# PROB_S7CAS_FPGA_3.net
KiCad netlist of a schematic drawn in Altium Designer
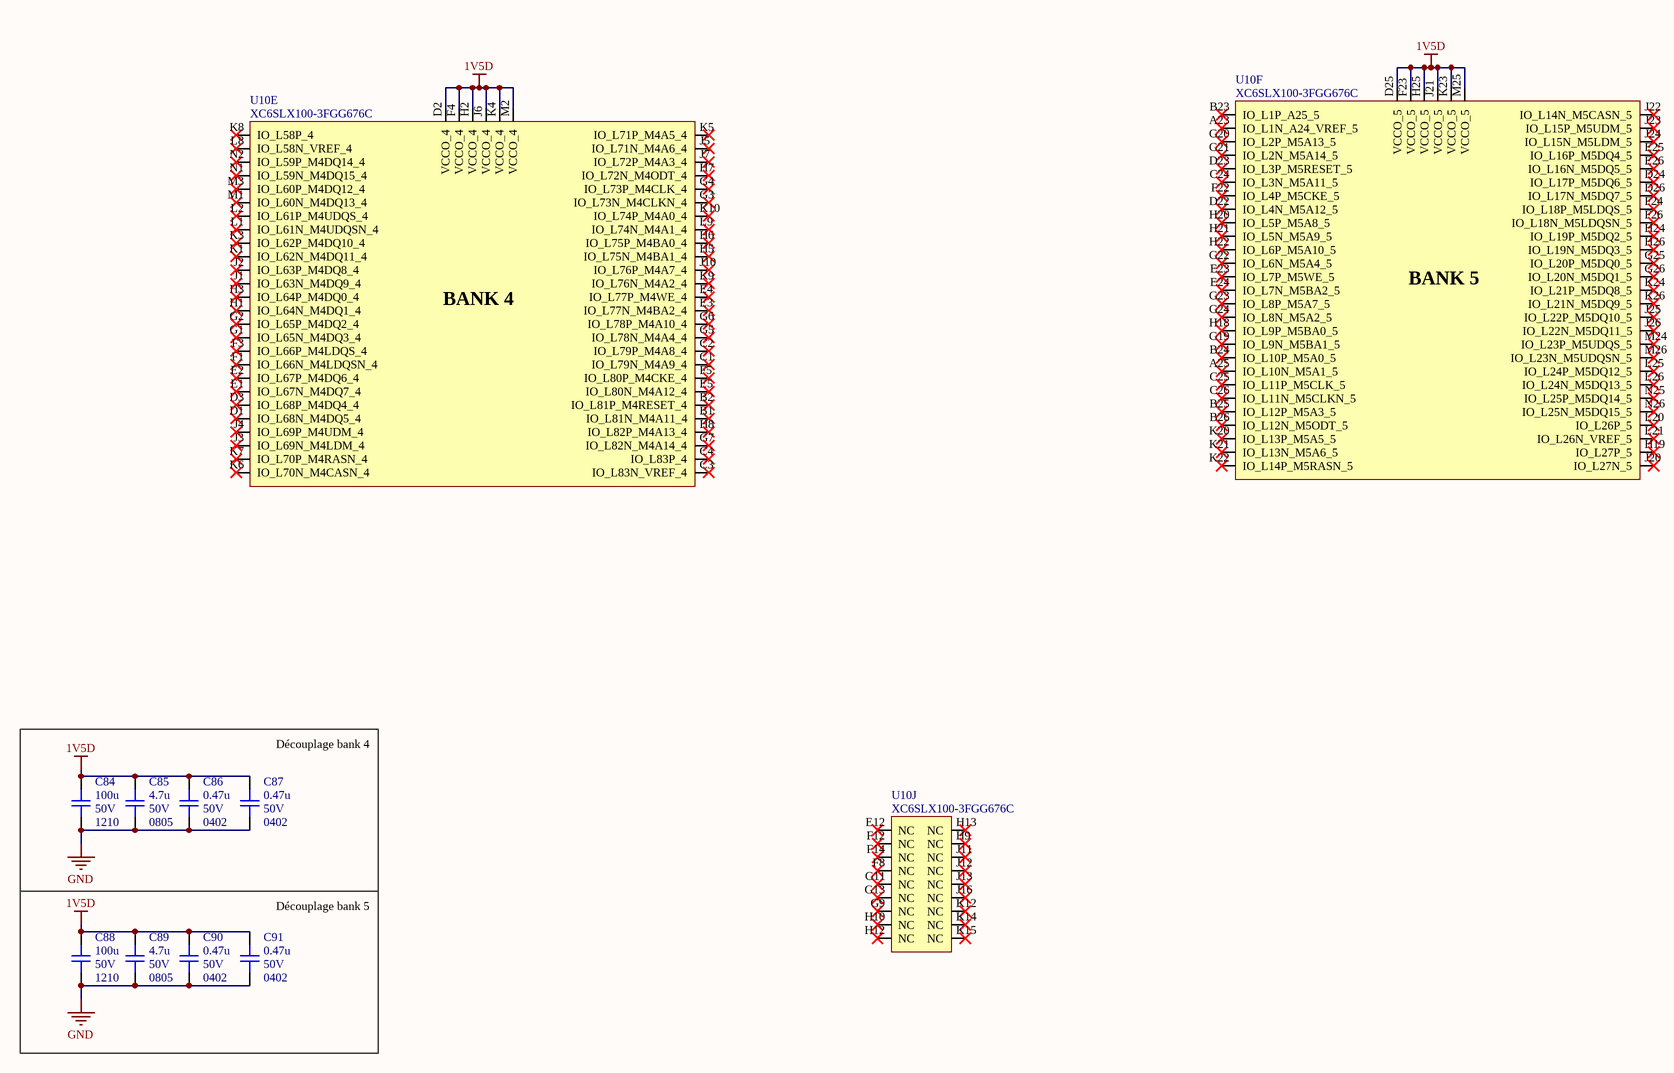
[diagram p0: PROB_S7CAS_FPGA_3.SchDoc]

(export (version "E")
  (design (tool "Eeschema 10.0.6"))
  (components
    (comp (ref "C84")
      (value "100u")
      (footprint "CAP_1210")
      (description "CAP - 1210")
      (fields
        (field (name "VOLTAGE") "50V")
        (field (name "PACKAGE") "1210")
        (field (name "CREATEDBY") "Jonathan Bouchard")
      )
      (libsource (lib "S7CAS_LIB2021") (part "CAP - 1210"))
    )
    (comp (ref "C85")
      (value "4.7u")
      (footprint "CAP_0805")
      (description "CAP - 0805")
      (fields
        (field (name "VOLTAGE") "50V")
        (field (name "PACKAGE") "0805")
        (field (name "CREATEDBY") "Jonathan Bouchard")
      )
      (libsource (lib "S7CAS_LIB2021") (part "CAP - 0805"))
    )
    (comp (ref "C86")
      (value "0.47u")
      (footprint "CAP_0402")
      (description "CAP - 0402")
      (fields
        (field (name "VOLTAGE") "50V")
        (field (name "PACKAGE") "0402")
        (field (name "CREATEDBY") "Jonathan Bouchard")
      )
      (libsource (lib "S7CAS_LIB2021") (part "CAP - 0402"))
    )
    (comp (ref "C87")
      (value "0.47u")
      (footprint "CAP_0402")
      (description "CAP - 0402")
      (fields
        (field (name "VOLTAGE") "50V")
        (field (name "PACKAGE") "0402")
        (field (name "CREATEDBY") "Jonathan Bouchard")
      )
      (libsource (lib "S7CAS_LIB2021") (part "CAP - 0402"))
    )
    (comp (ref "C88")
      (value "100u")
      (footprint "CAP_1210")
      (description "CAP - 1210")
      (fields
        (field (name "VOLTAGE") "50V")
        (field (name "PACKAGE") "1210")
        (field (name "CREATEDBY") "Jonathan Bouchard")
      )
      (libsource (lib "S7CAS_LIB2021") (part "CAP - 1210"))
    )
    (comp (ref "C89")
      (value "4.7u")
      (footprint "CAP_0805")
      (description "CAP - 0805")
      (fields
        (field (name "VOLTAGE") "50V")
        (field (name "PACKAGE") "0805")
        (field (name "CREATEDBY") "Jonathan Bouchard")
      )
      (libsource (lib "S7CAS_LIB2021") (part "CAP - 0805"))
    )
    (comp (ref "C90")
      (value "0.47u")
      (footprint "CAP_0402")
      (description "CAP - 0402")
      (fields
        (field (name "VOLTAGE") "50V")
        (field (name "PACKAGE") "0402")
        (field (name "CREATEDBY") "Jonathan Bouchard")
      )
      (libsource (lib "S7CAS_LIB2021") (part "CAP - 0402"))
    )
    (comp (ref "C91")
      (value "0.47u")
      (footprint "CAP_0402")
      (description "CAP - 0402")
      (fields
        (field (name "VOLTAGE") "50V")
        (field (name "PACKAGE") "0402")
        (field (name "CREATEDBY") "Jonathan Bouchard")
      )
      (libsource (lib "S7CAS_LIB2021") (part "CAP - 0402"))
    )
    (comp (ref "U10")
      (value "XC6SLX100-3FGG676C")
      (footprint "FPGA_XILINX_FGG676")
      (description "FPGA - XILINX SPARTAN 6 480 I/O - BGA-676")
      (fields
        (field (name "VOLTAGE") "1.14 V ~ 1.26 V")
        (field (name "MFG") "Xilinx")
        (field (name "CREATEDBY") "Jonathan Bouchard")
      )
      (libsource (lib "S7CAS_LIB2021") (part "FPGA_XC6SLX100-3FGG676C"))
    )
  )
  (nets
    (net (code "1") (name "1V5D") (class "Default")
      (node (ref "C84") (pin "2") (pinfunction "2_2") (pintype "passive"))
      (node (ref "C85") (pin "2") (pinfunction "2_2") (pintype "passive"))
      (node (ref "C86") (pin "2") (pinfunction "2_2") (pintype "passive"))
      (node (ref "C87") (pin "2") (pinfunction "2_2") (pintype "passive"))
      (node (ref "C88") (pin "2") (pinfunction "2_2") (pintype "passive"))
      (node (ref "C89") (pin "2") (pinfunction "2_2") (pintype "passive"))
      (node (ref "C90") (pin "2") (pinfunction "2_2") (pintype "passive"))
      (node (ref "C91") (pin "2") (pinfunction "2_2") (pintype "passive"))
      (node (ref "U10") (pin "D2") (pinfunction "VCCO_4_D2") (pintype "passive"))
      (node (ref "U10") (pin "D25") (pinfunction "VCCO_5_D25") (pintype "passive"))
      (node (ref "U10") (pin "F23") (pinfunction "VCCO_5_F23") (pintype "passive"))
      (node (ref "U10") (pin "F4") (pinfunction "VCCO_4_F4") (pintype "passive"))
      (node (ref "U10") (pin "H2") (pinfunction "VCCO_4_H2") (pintype "passive"))
      (node (ref "U10") (pin "H25") (pinfunction "VCCO_5_H25") (pintype "passive"))
      (node (ref "U10") (pin "J21") (pinfunction "VCCO_5_J21") (pintype "passive"))
      (node (ref "U10") (pin "J6") (pinfunction "VCCO_4_J6") (pintype "passive"))
      (node (ref "U10") (pin "K23") (pinfunction "VCCO_5_K23") (pintype "passive"))
      (node (ref "U10") (pin "K4") (pinfunction "VCCO_4_K4") (pintype "passive"))
      (node (ref "U10") (pin "M2") (pinfunction "VCCO_4_M2") (pintype "passive"))
      (node (ref "U10") (pin "M25") (pinfunction "VCCO_5_M25") (pintype "passive"))
    )
    (net (code "2") (name "GND") (class "Default")
      (node (ref "C84") (pin "1") (pinfunction "1_1") (pintype "passive"))
      (node (ref "C85") (pin "1") (pinfunction "1_1") (pintype "passive"))
      (node (ref "C86") (pin "1") (pinfunction "1_1") (pintype "passive"))
      (node (ref "C87") (pin "1") (pinfunction "1_1") (pintype "passive"))
      (node (ref "C88") (pin "1") (pinfunction "1_1") (pintype "passive"))
      (node (ref "C89") (pin "1") (pinfunction "1_1") (pintype "passive"))
      (node (ref "C90") (pin "1") (pinfunction "1_1") (pintype "passive"))
      (node (ref "C91") (pin "1") (pinfunction "1_1") (pintype "passive"))
    )
    (net (code "3") (name "unconnected-(U10E-IO_L58N_VREF_4-PadL8)") (class "Default")
      (node (ref "U10") (pin "L8") (pinfunction "IO_L58N_VREF_4_L8") (pintype "passive+no_connect"))
    )
    (net (code "4") (name "unconnected-(U10E-IO_L58P_4-PadK8)") (class "Default")
      (node (ref "U10") (pin "K8") (pinfunction "IO_L58P_4_K8") (pintype "passive+no_connect"))
    )
    (net (code "5") (name "unconnected-(U10E-IO_L59N_M4DQ15_4-PadN1)") (class "Default")
      (node (ref "U10") (pin "N1") (pinfunction "IO_L59N_M4DQ15_4_N1") (pintype "passive+no_connect"))
    )
    (net (code "6") (name "unconnected-(U10E-IO_L59P_M4DQ14_4-PadN2)") (class "Default")
      (node (ref "U10") (pin "N2") (pinfunction "IO_L59P_M4DQ14_4_N2") (pintype "passive+no_connect"))
    )
    (net (code "7") (name "unconnected-(U10E-IO_L60N_M4DQ13_4-PadM1)") (class "Default")
      (node (ref "U10") (pin "M1") (pinfunction "IO_L60N_M4DQ13_4_M1") (pintype "passive+no_connect"))
    )
    (net (code "8") (name "unconnected-(U10E-IO_L60P_M4DQ12_4-PadM3)") (class "Default")
      (node (ref "U10") (pin "M3") (pinfunction "IO_L60P_M4DQ12_4_M3") (pintype "passive+no_connect"))
    )
    (net (code "9") (name "unconnected-(U10E-IO_L61N_M4UDQSN_4-PadL1)") (class "Default")
      (node (ref "U10") (pin "L1") (pinfunction "IO_L61N_M4UDQSN_4_L1") (pintype "passive+no_connect"))
    )
    (net (code "10") (name "unconnected-(U10E-IO_L61P_M4UDQS_4-PadL2)") (class "Default")
      (node (ref "U10") (pin "L2") (pinfunction "IO_L61P_M4UDQS_4_L2") (pintype "passive+no_connect"))
    )
    (net (code "11") (name "unconnected-(U10E-IO_L62N_M4DQ11_4-PadK1)") (class "Default")
      (node (ref "U10") (pin "K1") (pinfunction "IO_L62N_M4DQ11_4_K1") (pintype "passive+no_connect"))
    )
    (net (code "12") (name "unconnected-(U10E-IO_L62P_M4DQ10_4-PadK3)") (class "Default")
      (node (ref "U10") (pin "K3") (pinfunction "IO_L62P_M4DQ10_4_K3") (pintype "passive+no_connect"))
    )
    (net (code "13") (name "unconnected-(U10E-IO_L63N_M4DQ9_4-PadJ1)") (class "Default")
      (node (ref "U10") (pin "J1") (pinfunction "IO_L63N_M4DQ9_4_J1") (pintype "passive+no_connect"))
    )
    (net (code "14") (name "unconnected-(U10E-IO_L63P_M4DQ8_4-PadJ2)") (class "Default")
      (node (ref "U10") (pin "J2") (pinfunction "IO_L63P_M4DQ8_4_J2") (pintype "passive+no_connect"))
    )
    (net (code "15") (name "unconnected-(U10E-IO_L64N_M4DQ1_4-PadH1)") (class "Default")
      (node (ref "U10") (pin "H1") (pinfunction "IO_L64N_M4DQ1_4_H1") (pintype "passive+no_connect"))
    )
    (net (code "16") (name "unconnected-(U10E-IO_L64P_M4DQ0_4-PadH3)") (class "Default")
      (node (ref "U10") (pin "H3") (pinfunction "IO_L64P_M4DQ0_4_H3") (pintype "passive+no_connect"))
    )
    (net (code "17") (name "unconnected-(U10E-IO_L65N_M4DQ3_4-PadG1)") (class "Default")
      (node (ref "U10") (pin "G1") (pinfunction "IO_L65N_M4DQ3_4_G1") (pintype "passive+no_connect"))
    )
    (net (code "18") (name "unconnected-(U10E-IO_L65P_M4DQ2_4-PadG2)") (class "Default")
      (node (ref "U10") (pin "G2") (pinfunction "IO_L65P_M4DQ2_4_G2") (pintype "passive+no_connect"))
    )
    (net (code "19") (name "unconnected-(U10E-IO_L66N_M4LDQSN_4-PadF1)") (class "Default")
      (node (ref "U10") (pin "F1") (pinfunction "IO_L66N_M4LDQSN_4_F1") (pintype "passive+no_connect"))
    )
    (net (code "20") (name "unconnected-(U10E-IO_L66P_M4LDQS_4-PadF3)") (class "Default")
      (node (ref "U10") (pin "F3") (pinfunction "IO_L66P_M4LDQS_4_F3") (pintype "passive+no_connect"))
    )
    (net (code "21") (name "unconnected-(U10E-IO_L67N_M4DQ7_4-PadE1)") (class "Default")
      (node (ref "U10") (pin "E1") (pinfunction "IO_L67N_M4DQ7_4_E1") (pintype "passive+no_connect"))
    )
    (net (code "22") (name "unconnected-(U10E-IO_L67P_M4DQ6_4-PadE2)") (class "Default")
      (node (ref "U10") (pin "E2") (pinfunction "IO_L67P_M4DQ6_4_E2") (pintype "passive+no_connect"))
    )
    (net (code "23") (name "unconnected-(U10E-IO_L68N_M4DQ5_4-PadD1)") (class "Default")
      (node (ref "U10") (pin "D1") (pinfunction "IO_L68N_M4DQ5_4_D1") (pintype "passive+no_connect"))
    )
    (net (code "24") (name "unconnected-(U10E-IO_L68P_M4DQ4_4-PadD3)") (class "Default")
      (node (ref "U10") (pin "D3") (pinfunction "IO_L68P_M4DQ4_4_D3") (pintype "passive+no_connect"))
    )
    (net (code "25") (name "unconnected-(U10E-IO_L69N_M4LDM_4-PadJ3)") (class "Default")
      (node (ref "U10") (pin "J3") (pinfunction "IO_L69N_M4LDM_4_J3") (pintype "passive+no_connect"))
    )
    (net (code "26") (name "unconnected-(U10E-IO_L69P_M4UDM_4-PadJ4)") (class "Default")
      (node (ref "U10") (pin "J4") (pinfunction "IO_L69P_M4UDM_4_J4") (pintype "passive+no_connect"))
    )
    (net (code "27") (name "unconnected-(U10E-IO_L70N_M4CASN_4-PadK6)") (class "Default")
      (node (ref "U10") (pin "K6") (pinfunction "IO_L70N_M4CASN_4_K6") (pintype "passive+no_connect"))
    )
    (net (code "28") (name "unconnected-(U10E-IO_L70P_M4RASN_4-PadK7)") (class "Default")
      (node (ref "U10") (pin "K7") (pinfunction "IO_L70P_M4RASN_4_K7") (pintype "passive+no_connect"))
    )
    (net (code "29") (name "unconnected-(U10E-IO_L71N_M4A6_4-PadJ5)") (class "Default")
      (node (ref "U10") (pin "J5") (pinfunction "IO_L71N_M4A6_4_J5") (pintype "passive+no_connect"))
    )
    (net (code "30") (name "unconnected-(U10E-IO_L71P_M4A5_4-PadK5)") (class "Default")
      (node (ref "U10") (pin "K5") (pinfunction "IO_L71P_M4A5_4_K5") (pintype "passive+no_connect"))
    )
    (net (code "31") (name "unconnected-(U10E-IO_L72N_M4ODT_4-PadH7)") (class "Default")
      (node (ref "U10") (pin "H7") (pinfunction "IO_L72N_M4ODT_4_H7") (pintype "passive+no_connect"))
    )
    (net (code "32") (name "unconnected-(U10E-IO_L72P_M4A3_4-PadJ7)") (class "Default")
      (node (ref "U10") (pin "J7") (pinfunction "IO_L72P_M4A3_4_J7") (pintype "passive+no_connect"))
    )
    (net (code "33") (name "unconnected-(U10E-IO_L73N_M4CLKN_4-PadG3)") (class "Default")
      (node (ref "U10") (pin "G3") (pinfunction "IO_L73N_M4CLKN_4_G3") (pintype "passive+no_connect"))
    )
    (net (code "34") (name "unconnected-(U10E-IO_L73P_M4CLK_4-PadG4)") (class "Default")
      (node (ref "U10") (pin "G4") (pinfunction "IO_L73P_M4CLK_4_G4") (pintype "passive+no_connect"))
    )
    (net (code "35") (name "unconnected-(U10E-IO_L74N_M4A1_4-PadL9)") (class "Default")
      (node (ref "U10") (pin "L9") (pinfunction "IO_L74N_M4A1_4_L9") (pintype "passive+no_connect"))
    )
    (net (code "36") (name "unconnected-(U10E-IO_L74P_M4A0_4-PadK10)") (class "Default")
      (node (ref "U10") (pin "K10") (pinfunction "IO_L74P_M4A0_4_K10") (pintype "passive+no_connect"))
    )
    (net (code "37") (name "unconnected-(U10E-IO_L75N_M4BA1_4-PadH5)") (class "Default")
      (node (ref "U10") (pin "H5") (pinfunction "IO_L75N_M4BA1_4_H5") (pintype "passive+no_connect"))
    )
    (net (code "38") (name "unconnected-(U10E-IO_L75P_M4BA0_4-PadH6)") (class "Default")
      (node (ref "U10") (pin "H6") (pinfunction "IO_L75P_M4BA0_4_H6") (pintype "passive+no_connect"))
    )
    (net (code "39") (name "unconnected-(U10E-IO_L76N_M4A2_4-PadK9)") (class "Default")
      (node (ref "U10") (pin "K9") (pinfunction "IO_L76N_M4A2_4_K9") (pintype "passive+no_connect"))
    )
    (net (code "40") (name "unconnected-(U10E-IO_L76P_M4A7_4-PadJ10)") (class "Default")
      (node (ref "U10") (pin "J10") (pinfunction "IO_L76P_M4A7_4_J10") (pintype "passive+no_connect"))
    )
    (net (code "41") (name "unconnected-(U10E-IO_L77N_M4BA2_4-PadE3)") (class "Default")
      (node (ref "U10") (pin "E3") (pinfunction "IO_L77N_M4BA2_4_E3") (pintype "passive+no_connect"))
    )
    (net (code "42") (name "unconnected-(U10E-IO_L77P_M4WE_4-PadE4)") (class "Default")
      (node (ref "U10") (pin "E4") (pinfunction "IO_L77P_M4WE_4_E4") (pintype "passive+no_connect"))
    )
    (net (code "43") (name "unconnected-(U10E-IO_L78N_M4A4_4-PadG5)") (class "Default")
      (node (ref "U10") (pin "G5") (pinfunction "IO_L78N_M4A4_4_G5") (pintype "passive+no_connect"))
    )
    (net (code "44") (name "unconnected-(U10E-IO_L78P_M4A10_4-PadG6)") (class "Default")
      (node (ref "U10") (pin "G6") (pinfunction "IO_L78P_M4A10_4_G6") (pintype "passive+no_connect"))
    )
    (net (code "45") (name "unconnected-(U10E-IO_L79N_M4A9_4-PadC1)") (class "Default")
      (node (ref "U10") (pin "C1") (pinfunction "IO_L79N_M4A9_4_C1") (pintype "passive+no_connect"))
    )
    (net (code "46") (name "unconnected-(U10E-IO_L79P_M4A8_4-PadC2)") (class "Default")
      (node (ref "U10") (pin "C2") (pinfunction "IO_L79P_M4A8_4_C2") (pintype "passive+no_connect"))
    )
    (net (code "47") (name "unconnected-(U10E-IO_L80N_M4A12_4-PadE5)") (class "Default")
      (node (ref "U10") (pin "E5") (pinfunction "IO_L80N_M4A12_4_E5") (pintype "passive+no_connect"))
    )
    (net (code "48") (name "unconnected-(U10E-IO_L80P_M4CKE_4-PadF5)") (class "Default")
      (node (ref "U10") (pin "F5") (pinfunction "IO_L80P_M4CKE_4_F5") (pintype "passive+no_connect"))
    )
    (net (code "49") (name "unconnected-(U10E-IO_L81N_M4A11_4-PadB1)") (class "Default")
      (node (ref "U10") (pin "B1") (pinfunction "IO_L81N_M4A11_4_B1") (pintype "passive+no_connect"))
    )
    (net (code "50") (name "unconnected-(U10E-IO_L81P_M4RESET_4-PadB2)") (class "Default")
      (node (ref "U10") (pin "B2") (pinfunction "IO_L81P_M4RESET_4_B2") (pintype "passive+no_connect"))
    )
    (net (code "51") (name "unconnected-(U10E-IO_L82N_M4A14_4-PadG7)") (class "Default")
      (node (ref "U10") (pin "G7") (pinfunction "IO_L82N_M4A14_4_G7") (pintype "passive+no_connect"))
    )
    (net (code "52") (name "unconnected-(U10E-IO_L82P_M4A13_4-PadH8)") (class "Default")
      (node (ref "U10") (pin "H8") (pinfunction "IO_L82P_M4A13_4_H8") (pintype "passive+no_connect"))
    )
    (net (code "53") (name "unconnected-(U10E-IO_L83N_VREF_4-PadC3)") (class "Default")
      (node (ref "U10") (pin "C3") (pinfunction "IO_L83N_VREF_4_C3") (pintype "passive+no_connect"))
    )
    (net (code "54") (name "unconnected-(U10E-IO_L83P_4-PadC4)") (class "Default")
      (node (ref "U10") (pin "C4") (pinfunction "IO_L83P_4_C4") (pintype "passive+no_connect"))
    )
    (net (code "55") (name "unconnected-(U10F-IO_L1N_A24_VREF_5-PadA23)") (class "Default")
      (node (ref "U10") (pin "A23") (pinfunction "IO_L1N_A24_VREF_5_A23") (pintype "passive+no_connect"))
    )
    (net (code "56") (name "unconnected-(U10F-IO_L1P_A25_5-PadB23)") (class "Default")
      (node (ref "U10") (pin "B23") (pinfunction "IO_L1P_A25_5_B23") (pintype "passive+no_connect"))
    )
    (net (code "57") (name "unconnected-(U10F-IO_L2N_M5A14_5-PadG21)") (class "Default")
      (node (ref "U10") (pin "G21") (pinfunction "IO_L2N_M5A14_5_G21") (pintype "passive+no_connect"))
    )
    (net (code "58") (name "unconnected-(U10F-IO_L2P_M5A13_5-PadG20)") (class "Default")
      (node (ref "U10") (pin "G20") (pinfunction "IO_L2P_M5A13_5_G20") (pintype "passive+no_connect"))
    )
    (net (code "59") (name "unconnected-(U10F-IO_L3N_M5A11_5-PadC24)") (class "Default")
      (node (ref "U10") (pin "C24") (pinfunction "IO_L3N_M5A11_5_C24") (pintype "passive+no_connect"))
    )
    (net (code "60") (name "unconnected-(U10F-IO_L3P_M5RESET_5-PadD23)") (class "Default")
      (node (ref "U10") (pin "D23") (pinfunction "IO_L3P_M5RESET_5_D23") (pintype "passive+no_connect"))
    )
    (net (code "61") (name "unconnected-(U10F-IO_L4N_M5A12_5-PadD22)") (class "Default")
      (node (ref "U10") (pin "D22") (pinfunction "IO_L4N_M5A12_5_D22") (pintype "passive+no_connect"))
    )
    (net (code "62") (name "unconnected-(U10F-IO_L4P_M5CKE_5-PadF22)") (class "Default")
      (node (ref "U10") (pin "F22") (pinfunction "IO_L4P_M5CKE_5_F22") (pintype "passive+no_connect"))
    )
    (net (code "63") (name "unconnected-(U10F-IO_L5N_M5A9_5-PadH21)") (class "Default")
      (node (ref "U10") (pin "H21") (pinfunction "IO_L5N_M5A9_5_H21") (pintype "passive+no_connect"))
    )
    (net (code "64") (name "unconnected-(U10F-IO_L5P_M5A8_5-PadH20)") (class "Default")
      (node (ref "U10") (pin "H20") (pinfunction "IO_L5P_M5A8_5_H20") (pintype "passive+no_connect"))
    )
    (net (code "65") (name "unconnected-(U10F-IO_L6N_M5A4_5-PadG22)") (class "Default")
      (node (ref "U10") (pin "G22") (pinfunction "IO_L6N_M5A4_5_G22") (pintype "passive+no_connect"))
    )
    (net (code "66") (name "unconnected-(U10F-IO_L6P_M5A10_5-PadH22)") (class "Default")
      (node (ref "U10") (pin "H22") (pinfunction "IO_L6P_M5A10_5_H22") (pintype "passive+no_connect"))
    )
    (net (code "67") (name "unconnected-(U10F-IO_L7N_M5BA2_5-PadE24)") (class "Default")
      (node (ref "U10") (pin "E24") (pinfunction "IO_L7N_M5BA2_5_E24") (pintype "passive+no_connect"))
    )
    (net (code "68") (name "unconnected-(U10F-IO_L7P_M5WE_5-PadE23)") (class "Default")
      (node (ref "U10") (pin "E23") (pinfunction "IO_L7P_M5WE_5_E23") (pintype "passive+no_connect"))
    )
    (net (code "69") (name "unconnected-(U10F-IO_L8N_M5A2_5-PadG24)") (class "Default")
      (node (ref "U10") (pin "G24") (pinfunction "IO_L8N_M5A2_5_G24") (pintype "passive+no_connect"))
    )
    (net (code "70") (name "unconnected-(U10F-IO_L8P_M5A7_5-PadG23)") (class "Default")
      (node (ref "U10") (pin "G23") (pinfunction "IO_L8P_M5A7_5_G23") (pintype "passive+no_connect"))
    )
    (net (code "71") (name "unconnected-(U10F-IO_L9N_M5BA1_5-PadG19)") (class "Default")
      (node (ref "U10") (pin "G19") (pinfunction "IO_L9N_M5BA1_5_G19") (pintype "passive+no_connect"))
    )
    (net (code "72") (name "unconnected-(U10F-IO_L9P_M5BA0_5-PadH18)") (class "Default")
      (node (ref "U10") (pin "H18") (pinfunction "IO_L9P_M5BA0_5_H18") (pintype "passive+no_connect"))
    )
    (net (code "73") (name "unconnected-(U10F-IO_L10N_M5A1_5-PadA25)") (class "Default")
      (node (ref "U10") (pin "A25") (pinfunction "IO_L10N_M5A1_5_A25") (pintype "passive+no_connect"))
    )
    (net (code "74") (name "unconnected-(U10F-IO_L10P_M5A0_5-PadB24)") (class "Default")
      (node (ref "U10") (pin "B24") (pinfunction "IO_L10P_M5A0_5_B24") (pintype "passive+no_connect"))
    )
    (net (code "75") (name "unconnected-(U10F-IO_L11N_M5CLKN_5-PadC26)") (class "Default")
      (node (ref "U10") (pin "C26") (pinfunction "IO_L11N_M5CLKN_5_C26") (pintype "passive+no_connect"))
    )
    (net (code "76") (name "unconnected-(U10F-IO_L11P_M5CLK_5-PadC25)") (class "Default")
      (node (ref "U10") (pin "C25") (pinfunction "IO_L11P_M5CLK_5_C25") (pintype "passive+no_connect"))
    )
    (net (code "77") (name "unconnected-(U10F-IO_L12N_M5ODT_5-PadB26)") (class "Default")
      (node (ref "U10") (pin "B26") (pinfunction "IO_L12N_M5ODT_5_B26") (pintype "passive+no_connect"))
    )
    (net (code "78") (name "unconnected-(U10F-IO_L12P_M5A3_5-PadB25)") (class "Default")
      (node (ref "U10") (pin "B25") (pinfunction "IO_L12P_M5A3_5_B25") (pintype "passive+no_connect"))
    )
    (net (code "79") (name "unconnected-(U10F-IO_L13N_M5A6_5-PadK21)") (class "Default")
      (node (ref "U10") (pin "K21") (pinfunction "IO_L13N_M5A6_5_K21") (pintype "passive+no_connect"))
    )
    (net (code "80") (name "unconnected-(U10F-IO_L13P_M5A5_5-PadK20)") (class "Default")
      (node (ref "U10") (pin "K20") (pinfunction "IO_L13P_M5A5_5_K20") (pintype "passive+no_connect"))
    )
    (net (code "81") (name "unconnected-(U10F-IO_L14N_M5CASN_5-PadJ22)") (class "Default")
      (node (ref "U10") (pin "J22") (pinfunction "IO_L14N_M5CASN_5_J22") (pintype "passive+no_connect"))
    )
    (net (code "82") (name "unconnected-(U10F-IO_L14P_M5RASN_5-PadK22)") (class "Default")
      (node (ref "U10") (pin "K22") (pinfunction "IO_L14P_M5RASN_5_K22") (pintype "passive+no_connect"))
    )
    (net (code "83") (name "unconnected-(U10F-IO_L15N_M5LDM_5-PadJ24)") (class "Default")
      (node (ref "U10") (pin "J24") (pinfunction "IO_L15N_M5LDM_5_J24") (pintype "passive+no_connect"))
    )
    (net (code "84") (name "unconnected-(U10F-IO_L15P_M5UDM_5-PadJ23)") (class "Default")
      (node (ref "U10") (pin "J23") (pinfunction "IO_L15P_M5UDM_5_J23") (pintype "passive+no_connect"))
    )
    (net (code "85") (name "unconnected-(U10F-IO_L16N_M5DQ5_5-PadE26)") (class "Default")
      (node (ref "U10") (pin "E26") (pinfunction "IO_L16N_M5DQ5_5_E26") (pintype "passive+no_connect"))
    )
    (net (code "86") (name "unconnected-(U10F-IO_L16P_M5DQ4_5-PadE25)") (class "Default")
      (node (ref "U10") (pin "E25") (pinfunction "IO_L16P_M5DQ4_5_E25") (pintype "passive+no_connect"))
    )
    (net (code "87") (name "unconnected-(U10F-IO_L17N_M5DQ7_5-PadD26)") (class "Default")
      (node (ref "U10") (pin "D26") (pinfunction "IO_L17N_M5DQ7_5_D26") (pintype "passive+no_connect"))
    )
    (net (code "88") (name "unconnected-(U10F-IO_L17P_M5DQ6_5-PadD24)") (class "Default")
      (node (ref "U10") (pin "D24") (pinfunction "IO_L17P_M5DQ6_5_D24") (pintype "passive+no_connect"))
    )
    (net (code "89") (name "unconnected-(U10F-IO_L18N_M5LDQSN_5-PadF26)") (class "Default")
      (node (ref "U10") (pin "F26") (pinfunction "IO_L18N_M5LDQSN_5_F26") (pintype "passive+no_connect"))
    )
    (net (code "90") (name "unconnected-(U10F-IO_L18P_M5LDQS_5-PadF24)") (class "Default")
      (node (ref "U10") (pin "F24") (pinfunction "IO_L18P_M5LDQS_5_F24") (pintype "passive+no_connect"))
    )
    (net (code "91") (name "unconnected-(U10F-IO_L19N_M5DQ3_5-PadH26)") (class "Default")
      (node (ref "U10") (pin "H26") (pinfunction "IO_L19N_M5DQ3_5_H26") (pintype "passive+no_connect"))
    )
    (net (code "92") (name "unconnected-(U10F-IO_L19P_M5DQ2_5-PadH24)") (class "Default")
      (node (ref "U10") (pin "H24") (pinfunction "IO_L19P_M5DQ2_5_H24") (pintype "passive+no_connect"))
    )
    (net (code "93") (name "unconnected-(U10F-IO_L20N_M5DQ1_5-PadG26)") (class "Default")
      (node (ref "U10") (pin "G26") (pinfunction "IO_L20N_M5DQ1_5_G26") (pintype "passive+no_connect"))
    )
    (net (code "94") (name "unconnected-(U10F-IO_L20P_M5DQ0_5-PadG25)") (class "Default")
      (node (ref "U10") (pin "G25") (pinfunction "IO_L20P_M5DQ0_5_G25") (pintype "passive+no_connect"))
    )
    (net (code "95") (name "unconnected-(U10F-IO_L21N_M5DQ9_5-PadK26)") (class "Default")
      (node (ref "U10") (pin "K26") (pinfunction "IO_L21N_M5DQ9_5_K26") (pintype "passive+no_connect"))
    )
    (net (code "96") (name "unconnected-(U10F-IO_L21P_M5DQ8_5-PadK24)") (class "Default")
      (node (ref "U10") (pin "K24") (pinfunction "IO_L21P_M5DQ8_5_K24") (pintype "passive+no_connect"))
    )
    (net (code "97") (name "unconnected-(U10F-IO_L22N_M5DQ11_5-PadJ26)") (class "Default")
      (node (ref "U10") (pin "J26") (pinfunction "IO_L22N_M5DQ11_5_J26") (pintype "passive+no_connect"))
    )
    (net (code "98") (name "unconnected-(U10F-IO_L22P_M5DQ10_5-PadJ25)") (class "Default")
      (node (ref "U10") (pin "J25") (pinfunction "IO_L22P_M5DQ10_5_J25") (pintype "passive+no_connect"))
    )
    (net (code "99") (name "unconnected-(U10F-IO_L23N_M5UDQSN_5-PadM26)") (class "Default")
      (node (ref "U10") (pin "M26") (pinfunction "IO_L23N_M5UDQSN_5_M26") (pintype "passive+no_connect"))
    )
    (net (code "100") (name "unconnected-(U10F-IO_L23P_M5UDQS_5-PadM24)") (class "Default")
      (node (ref "U10") (pin "M24") (pinfunction "IO_L23P_M5UDQS_5_M24") (pintype "passive+no_connect"))
    )
    (net (code "101") (name "unconnected-(U10F-IO_L24N_M5DQ13_5-PadL26)") (class "Default")
      (node (ref "U10") (pin "L26") (pinfunction "IO_L24N_M5DQ13_5_L26") (pintype "passive+no_connect"))
    )
    (net (code "102") (name "unconnected-(U10F-IO_L24P_M5DQ12_5-PadL25)") (class "Default")
      (node (ref "U10") (pin "L25") (pinfunction "IO_L24P_M5DQ12_5_L25") (pintype "passive+no_connect"))
    )
    (net (code "103") (name "unconnected-(U10F-IO_L25N_M5DQ15_5-PadN26)") (class "Default")
      (node (ref "U10") (pin "N26") (pinfunction "IO_L25N_M5DQ15_5_N26") (pintype "passive+no_connect"))
    )
    (net (code "104") (name "unconnected-(U10F-IO_L25P_M5DQ14_5-PadN25)") (class "Default")
      (node (ref "U10") (pin "N25") (pinfunction "IO_L25P_M5DQ14_5_N25") (pintype "passive+no_connect"))
    )
    (net (code "105") (name "unconnected-(U10F-IO_L26N_VREF_5-PadL21)") (class "Default")
      (node (ref "U10") (pin "L21") (pinfunction "IO_L26N_VREF_5_L21") (pintype "passive+no_connect"))
    )
    (net (code "106") (name "unconnected-(U10F-IO_L26P_5-PadL20)") (class "Default")
      (node (ref "U10") (pin "L20") (pinfunction "IO_L26P_5_L20") (pintype "passive+no_connect"))
    )
    (net (code "107") (name "unconnected-(U10F-IO_L27N_5-PadJ20)") (class "Default")
      (node (ref "U10") (pin "J20") (pinfunction "IO_L27N_5_J20") (pintype "passive+no_connect"))
    )
    (net (code "108") (name "unconnected-(U10F-IO_L27P_5-PadH19)") (class "Default")
      (node (ref "U10") (pin "H19") (pinfunction "IO_L27P_5_H19") (pintype "passive+no_connect"))
    )
    (net (code "109") (name "unconnected-(U10J-NC-PadE12)") (class "Default")
      (node (ref "U10") (pin "E12") (pinfunction "NC_E12") (pintype "passive+no_connect"))
    )
    (net (code "110") (name "unconnected-(U10J-NC-PadF8)") (class "Default")
      (node (ref "U10") (pin "F8") (pinfunction "NC_F8") (pintype "passive+no_connect"))
    )
    (net (code "111") (name "unconnected-(U10J-NC-PadF12)") (class "Default")
      (node (ref "U10") (pin "F12") (pinfunction "NC_F12") (pintype "passive+no_connect"))
    )
    (net (code "112") (name "unconnected-(U10J-NC-PadF14)") (class "Default")
      (node (ref "U10") (pin "F14") (pinfunction "NC_F14") (pintype "passive+no_connect"))
    )
    (net (code "113") (name "unconnected-(U10J-NC-PadG9)") (class "Default")
      (node (ref "U10") (pin "G9") (pinfunction "NC_G9") (pintype "passive+no_connect"))
    )
    (net (code "114") (name "unconnected-(U10J-NC-PadG11)") (class "Default")
      (node (ref "U10") (pin "G11") (pinfunction "NC_G11") (pintype "passive+no_connect"))
    )
    (net (code "115") (name "unconnected-(U10J-NC-PadG13)") (class "Default")
      (node (ref "U10") (pin "G13") (pinfunction "NC_G13") (pintype "passive+no_connect"))
    )
    (net (code "116") (name "unconnected-(U10J-NC-PadH9)") (class "Default")
      (node (ref "U10") (pin "H9") (pinfunction "NC_H9") (pintype "passive+no_connect"))
    )
    (net (code "117") (name "unconnected-(U10J-NC-PadH10)") (class "Default")
      (node (ref "U10") (pin "H10") (pinfunction "NC_H10") (pintype "passive+no_connect"))
    )
    (net (code "118") (name "unconnected-(U10J-NC-PadH12)") (class "Default")
      (node (ref "U10") (pin "H12") (pinfunction "NC_H12") (pintype "passive+no_connect"))
    )
    (net (code "119") (name "unconnected-(U10J-NC-PadH13)") (class "Default")
      (node (ref "U10") (pin "H13") (pinfunction "NC_H13") (pintype "passive+no_connect"))
    )
    (net (code "120") (name "unconnected-(U10J-NC-PadJ11)") (class "Default")
      (node (ref "U10") (pin "J11") (pinfunction "NC_J11") (pintype "passive+no_connect"))
    )
    (net (code "121") (name "unconnected-(U10J-NC-PadJ12)") (class "Default")
      (node (ref "U10") (pin "J12") (pinfunction "NC_J12") (pintype "passive+no_connect"))
    )
    (net (code "122") (name "unconnected-(U10J-NC-PadJ13)") (class "Default")
      (node (ref "U10") (pin "J13") (pinfunction "NC_J13") (pintype "passive+no_connect"))
    )
    (net (code "123") (name "unconnected-(U10J-NC-PadJ16)") (class "Default")
      (node (ref "U10") (pin "J16") (pinfunction "NC_J16") (pintype "passive+no_connect"))
    )
    (net (code "124") (name "unconnected-(U10J-NC-PadK12)") (class "Default")
      (node (ref "U10") (pin "K12") (pinfunction "NC_K12") (pintype "passive+no_connect"))
    )
    (net (code "125") (name "unconnected-(U10J-NC-PadK14)") (class "Default")
      (node (ref "U10") (pin "K14") (pinfunction "NC_K14") (pintype "passive+no_connect"))
    )
    (net (code "126") (name "unconnected-(U10J-NC-PadK15)") (class "Default")
      (node (ref "U10") (pin "K15") (pinfunction "NC_K15") (pintype "passive+no_connect"))
    )
  )
)
